# SD.net
KiCad netlist of a schematic drawn in Altium Designer
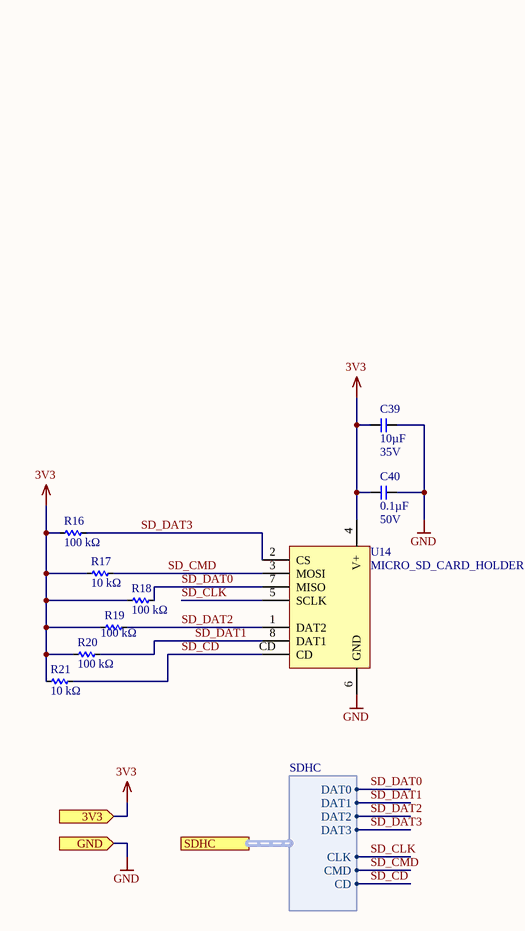
[diagram p0: SD.SchDoc]

(export (version "E")
  (design (tool "Eeschema 10.0.6"))
  (components
    (comp (ref "C39")
      (value "490-13248-1-ND")
      (footprint "C0603")
      (description "CAP CER 10UF 35V X5R 0603 20%")
      (fields
        (field (name "CAPACITANCE (SHORTHAND)") "10µF")
        (field (name "RATED VOLTAGE") "35V")
        (field (name "MANUFACTURER") "Murata Electronics North America")
      )
      (libsource (lib "Stanford Student Space Initiative") (part "__template_cap"))
    )
    (comp (ref "C40")
      (value "490-1519-1-ND")
      (footprint "C0603")
      (description "CAP CER 0603 0.1µF X7R 50V 10%")
      (fields
        (field (name "CAPACITANCE (SHORTHAND)") "0.1µF")
        (field (name "RATED VOLTAGE") "50V")
        (field (name "MANUFACTURER") "Murata Electronics North America")
      )
      (libsource (lib "Stanford Student Space Initiative") (part "__template_cap"))
    )
    (comp (ref "R16")
      (value "311-100KHRCT-ND")
      (footprint "R0603")
      (description "RES SMD 100K OHM 1% 1/10W 0603")
      (fields
        (field (name "RESISTANCE") "100 kΩ")
        (field (name "MANUFACTURER PART NUMBER") "RC0603FR-07100KL")
        (field (name "MANUFACTURER") "Yageo")
      )
      (libsource (lib "Stanford Student Space Initiative") (part "__template_resistor"))
    )
    (comp (ref "R17")
      (value "311-10.0KHRCT-ND")
      (footprint "R0603")
      (description "RES SMD 10K OHM 1% 1/10W 0603")
      (fields
        (field (name "RESISTANCE") "10 kΩ")
        (field (name "MANUFACTURER PART NUMBER") "RC0603FR-0710KL")
        (field (name "MANUFACTURER") "Yageo")
      )
      (libsource (lib "Stanford Student Space Initiative") (part "__template_resistor"))
    )
    (comp (ref "R18")
      (value "311-100KHRCT-ND")
      (footprint "R0603")
      (description "RES SMD 100K OHM 1% 1/10W 0603")
      (fields
        (field (name "RESISTANCE") "100 kΩ")
        (field (name "MANUFACTURER PART NUMBER") "RC0603FR-07100KL")
        (field (name "MANUFACTURER") "Yageo")
      )
      (libsource (lib "Stanford Student Space Initiative") (part "__template_resistor"))
    )
    (comp (ref "R19")
      (value "311-100KHRCT-ND")
      (footprint "R0603")
      (description "RES SMD 100K OHM 1% 1/10W 0603")
      (fields
        (field (name "RESISTANCE") "100 kΩ")
        (field (name "MANUFACTURER PART NUMBER") "RC0603FR-07100KL")
        (field (name "MANUFACTURER") "Yageo")
      )
      (libsource (lib "Stanford Student Space Initiative") (part "__template_resistor"))
    )
    (comp (ref "R20")
      (value "311-100KHRCT-ND")
      (footprint "R0603")
      (description "RES SMD 100K OHM 1% 1/10W 0603")
      (fields
        (field (name "RESISTANCE") "100 kΩ")
        (field (name "MANUFACTURER PART NUMBER") "RC0603FR-07100KL")
        (field (name "MANUFACTURER") "Yageo")
      )
      (libsource (lib "Stanford Student Space Initiative") (part "__template_resistor"))
    )
    (comp (ref "R21")
      (value "311-10.0KHRCT-ND")
      (footprint "R0603")
      (description "RES SMD 10K OHM 1% 1/10W 0603")
      (fields
        (field (name "RESISTANCE") "10 kΩ")
        (field (name "MANUFACTURER PART NUMBER") "RC0603FR-0710KL")
        (field (name "MANUFACTURER") "Yageo")
      )
      (libsource (lib "Stanford Student Space Initiative") (part "__template_resistor"))
    )
    (comp (ref "U14")
      (value "MICRO_SD_CARD_HOLDER")
      (footprint "MICROSD_CARD_SOCKET")
      (description "MICROSD CARD HOLDER, PUSH-PUSH")
      (fields (field (name "MANUFACTURER") "3M") (field (name "MANUFACTURER PART NUMBER") "2908-05WB-MG"))
      (libsource (lib "Stanford Student Space Initiative") (part "MICRO_SD_CARD_HOLDER"))
    )
  )
  (nets
    (net (code "2") (name "/SD_CD") (class "Default")
      (node (ref "R21") (pin "2") (pinfunction "2_2") (pintype "passive"))
      (node (ref "U14") (pin "CD") (pinfunction "CD_CD") (pintype "passive"))
    )
    (net (code "3") (name "/SD_CLK") (class "Default")
      (node (ref "U14") (pin "5") (pinfunction "SCLK_5") (pintype "passive"))
    )
    (net (code "4") (name "/SD_CMD") (class "Default")
      (node (ref "R17") (pin "2") (pinfunction "2_2") (pintype "passive"))
      (node (ref "U14") (pin "3") (pinfunction "MOSI_3") (pintype "passive"))
    )
    (net (code "5") (name "/SD_DAT0") (class "Default")
      (node (ref "R18") (pin "2") (pinfunction "2_2") (pintype "passive"))
      (node (ref "U14") (pin "7") (pinfunction "MISO_7") (pintype "passive"))
    )
    (net (code "6") (name "/SD_DAT1") (class "Default")
      (node (ref "R20") (pin "2") (pinfunction "2_2") (pintype "passive"))
      (node (ref "U14") (pin "8") (pinfunction "DAT1_8") (pintype "passive"))
    )
    (net (code "7") (name "/SD_DAT2") (class "Default")
      (node (ref "R19") (pin "2") (pinfunction "2_2") (pintype "passive"))
      (node (ref "U14") (pin "1") (pinfunction "DAT2_1") (pintype "passive"))
    )
    (net (code "8") (name "/SD_DAT3") (class "Default")
      (node (ref "R16") (pin "2") (pinfunction "2_2") (pintype "passive"))
      (node (ref "U14") (pin "2") (pinfunction "CS_2") (pintype "passive"))
    )
    (net (code "10") (name "3V3") (class "Default")
      (node (ref "C39") (pin "2") (pintype "passive"))
      (node (ref "C40") (pin "1") (pintype "passive"))
      (node (ref "R16") (pin "1") (pinfunction "1_1") (pintype "passive"))
      (node (ref "R17") (pin "1") (pinfunction "1_1") (pintype "passive"))
      (node (ref "R18") (pin "1") (pinfunction "1_1") (pintype "passive"))
      (node (ref "R19") (pin "1") (pinfunction "1_1") (pintype "passive"))
      (node (ref "R20") (pin "1") (pinfunction "1_1") (pintype "passive"))
      (node (ref "R21") (pin "1") (pinfunction "1_1") (pintype "passive"))
      (node (ref "U14") (pin "4") (pinfunction "V+_4") (pintype "passive"))
    )
    (net (code "11") (name "GND") (class "Default")
      (node (ref "C39") (pin "1") (pintype "passive"))
      (node (ref "C40") (pin "2") (pintype "passive"))
      (node (ref "U14") (pin "6") (pinfunction "GND_6") (pintype "passive"))
    )
  )
)
